# 07_-_CONNECTOR.net
KiCad netlist of a schematic drawn in Altium Designer
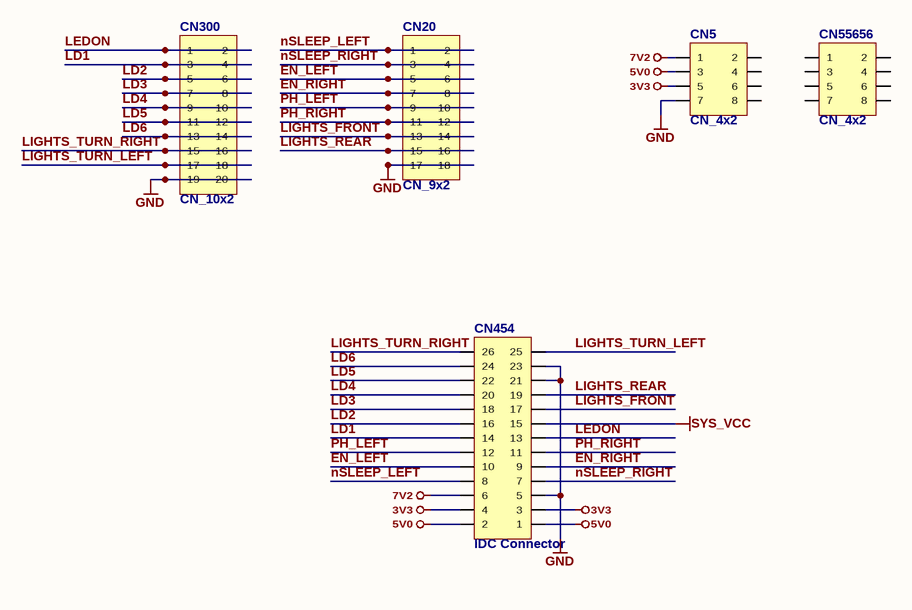
[diagram p0: [07] - CONNECTOR.SchDoc]

(export (version "E")
  (design (tool "Eeschema 10.0.6"))
  (components
    (comp (ref "CN5") (value "CN_4x2") (footprint "GP_4x2") (libsource (lib "goldpin_male") (part "CN_4x2")))
    (comp (ref "CN20") (value "CN_9x2") (footprint "GP_9x2") (libsource (lib "goldpin_male") (part "CN_9x2")))
    (comp (ref "CN300")
      (value "CN_10x2")
      (footprint "GP_10x2")
      (libsource (lib "goldpin_male") (part "CN_10x2"))
    )
    (comp (ref "CN454")
      (value "IDC Connector")
      (footprint "IDC26_RA")
      (libsource (lib "idc") (part "CN_13x2"))
    )
    (comp (ref "CN55656")
      (value "CN_4x2")
      (footprint "GP_4x2")
      (libsource (lib "goldpin_male") (part "CN_4x2"))
    )
  )
  (nets
    (net (code "1") (name "/EN_LEFT") (class "Default")
      (node (ref "CN20") (pin "5") (pinfunction "5_5") (pintype "passive"))
      (node (ref "CN20") (pin "6") (pinfunction "6_6") (pintype "passive"))
      (node (ref "CN454") (pin "10") (pinfunction "10_10") (pintype "passive"))
    )
    (net (code "2") (name "/EN_RIGHT") (class "Default")
      (node (ref "CN20") (pin "7") (pinfunction "7_7") (pintype "passive"))
      (node (ref "CN20") (pin "8") (pinfunction "8_8") (pintype "passive"))
      (node (ref "CN454") (pin "9") (pinfunction "9_9") (pintype "passive"))
    )
    (net (code "3") (name "/LD1") (class "Default")
      (node (ref "CN300") (pin "3") (pinfunction "3_3") (pintype "passive"))
      (node (ref "CN300") (pin "4") (pinfunction "4_4") (pintype "passive"))
      (node (ref "CN454") (pin "14") (pinfunction "14_14") (pintype "passive"))
    )
    (net (code "4") (name "/LD2") (class "Default")
      (node (ref "CN300") (pin "5") (pinfunction "5_5") (pintype "passive"))
      (node (ref "CN300") (pin "6") (pinfunction "6_6") (pintype "passive"))
      (node (ref "CN454") (pin "16") (pinfunction "16_16") (pintype "passive"))
    )
    (net (code "5") (name "/LD3") (class "Default")
      (node (ref "CN300") (pin "7") (pinfunction "7_7") (pintype "passive"))
      (node (ref "CN300") (pin "8") (pinfunction "8_8") (pintype "passive"))
      (node (ref "CN454") (pin "18") (pinfunction "18_18") (pintype "passive"))
    )
    (net (code "6") (name "/LD4") (class "Default")
      (node (ref "CN300") (pin "10") (pinfunction "10_10") (pintype "passive"))
      (node (ref "CN300") (pin "9") (pinfunction "9_9") (pintype "passive"))
      (node (ref "CN454") (pin "20") (pinfunction "20_20") (pintype "passive"))
    )
    (net (code "7") (name "/LD5") (class "Default")
      (node (ref "CN300") (pin "11") (pinfunction "11_11") (pintype "passive"))
      (node (ref "CN300") (pin "12") (pinfunction "12_12") (pintype "passive"))
      (node (ref "CN454") (pin "22") (pinfunction "22_22") (pintype "passive"))
    )
    (net (code "8") (name "/LD6") (class "Default")
      (node (ref "CN300") (pin "13") (pinfunction "13_13") (pintype "passive"))
      (node (ref "CN300") (pin "14") (pinfunction "14_14") (pintype "passive"))
      (node (ref "CN454") (pin "24") (pinfunction "24_24") (pintype "passive"))
    )
    (net (code "9") (name "/LEDON") (class "Default")
      (node (ref "CN300") (pin "1") (pinfunction "1_1") (pintype "passive"))
      (node (ref "CN300") (pin "2") (pinfunction "2_2") (pintype "passive"))
      (node (ref "CN454") (pin "13") (pinfunction "13_13") (pintype "passive"))
    )
    (net (code "10") (name "/LIGHTS_FRONT") (class "Default")
      (node (ref "CN20") (pin "13") (pinfunction "13_13") (pintype "passive"))
      (node (ref "CN20") (pin "14") (pinfunction "14_14") (pintype "passive"))
      (node (ref "CN454") (pin "17") (pinfunction "17_17") (pintype "passive"))
    )
    (net (code "11") (name "/LIGHTS_REAR") (class "Default")
      (node (ref "CN20") (pin "15") (pinfunction "15_15") (pintype "passive"))
      (node (ref "CN20") (pin "16") (pinfunction "16_16") (pintype "passive"))
      (node (ref "CN454") (pin "19") (pinfunction "19_19") (pintype "passive"))
    )
    (net (code "12") (name "/LIGHTS_TURN_LEFT") (class "Default")
      (node (ref "CN300") (pin "17") (pinfunction "17_17") (pintype "passive"))
      (node (ref "CN300") (pin "18") (pinfunction "18_18") (pintype "passive"))
      (node (ref "CN454") (pin "25") (pinfunction "25_25") (pintype "passive"))
    )
    (net (code "13") (name "/LIGHTS_TURN_RIGHT") (class "Default")
      (node (ref "CN300") (pin "15") (pinfunction "15_15") (pintype "passive"))
      (node (ref "CN300") (pin "16") (pinfunction "16_16") (pintype "passive"))
      (node (ref "CN454") (pin "26") (pinfunction "26_26") (pintype "passive"))
    )
    (net (code "14") (name "/PH_LEFT") (class "Default")
      (node (ref "CN20") (pin "10") (pinfunction "10_10") (pintype "passive"))
      (node (ref "CN20") (pin "9") (pinfunction "9_9") (pintype "passive"))
      (node (ref "CN454") (pin "12") (pinfunction "12_12") (pintype "passive"))
    )
    (net (code "15") (name "/PH_RIGHT") (class "Default")
      (node (ref "CN20") (pin "11") (pinfunction "11_11") (pintype "passive"))
      (node (ref "CN20") (pin "12") (pinfunction "12_12") (pintype "passive"))
      (node (ref "CN454") (pin "11") (pinfunction "11_11") (pintype "passive"))
    )
    (net (code "16") (name "/nSLEEP_LEFT") (class "Default")
      (node (ref "CN20") (pin "1") (pinfunction "1_1") (pintype "passive"))
      (node (ref "CN20") (pin "2") (pinfunction "2_2") (pintype "passive"))
      (node (ref "CN454") (pin "8") (pinfunction "8_8") (pintype "passive"))
    )
    (net (code "17") (name "/nSLEEP_RIGHT") (class "Default")
      (node (ref "CN20") (pin "3") (pinfunction "3_3") (pintype "passive"))
      (node (ref "CN20") (pin "4") (pinfunction "4_4") (pintype "passive"))
      (node (ref "CN454") (pin "7") (pinfunction "7_7") (pintype "passive"))
    )
    (net (code "18") (name "3V3") (class "Default")
      (node (ref "CN454") (pin "3") (pinfunction "3_3") (pintype "passive"))
      (node (ref "CN454") (pin "4") (pinfunction "4_4") (pintype "passive"))
      (node (ref "CN5") (pin "5") (pinfunction "5_5") (pintype "passive"))
    )
    (net (code "19") (name "5V0") (class "Default")
      (node (ref "CN454") (pin "1") (pinfunction "1_1") (pintype "passive"))
      (node (ref "CN454") (pin "2") (pinfunction "2_2") (pintype "passive"))
      (node (ref "CN5") (pin "3") (pinfunction "3_3") (pintype "passive"))
    )
    (net (code "20") (name "7V2") (class "Default")
      (node (ref "CN454") (pin "6") (pinfunction "6_6") (pintype "passive"))
      (node (ref "CN5") (pin "1") (pinfunction "1_1") (pintype "passive"))
    )
    (net (code "21") (name "GND") (class "Default")
      (node (ref "CN20") (pin "17") (pinfunction "17_17") (pintype "passive"))
      (node (ref "CN20") (pin "18") (pinfunction "18_18") (pintype "passive"))
      (node (ref "CN300") (pin "19") (pinfunction "19_19") (pintype "passive"))
      (node (ref "CN300") (pin "20") (pinfunction "20_20") (pintype "passive"))
      (node (ref "CN454") (pin "21") (pinfunction "21_21") (pintype "passive"))
      (node (ref "CN454") (pin "23") (pinfunction "23_23") (pintype "passive"))
      (node (ref "CN454") (pin "5") (pinfunction "5_5") (pintype "passive"))
      (node (ref "CN5") (pin "7") (pinfunction "7_7") (pintype "passive"))
    )
    (net (code "22") (name "SYS_VCC") (class "Default")
      (node (ref "CN454") (pin "15") (pinfunction "15_15") (pintype "passive"))
    )
    (net (code "23") (name "unconnected-(CN5-Pad2)") (class "Default")
      (node (ref "CN5") (pin "2") (pinfunction "2_2") (pintype "passive"))
    )
    (net (code "24") (name "unconnected-(CN5-Pad4)") (class "Default")
      (node (ref "CN5") (pin "4") (pinfunction "4_4") (pintype "passive"))
    )
    (net (code "25") (name "unconnected-(CN5-Pad6)") (class "Default")
      (node (ref "CN5") (pin "6") (pinfunction "6_6") (pintype "passive"))
    )
    (net (code "26") (name "unconnected-(CN5-Pad8)") (class "Default")
      (node (ref "CN5") (pin "8") (pinfunction "8_8") (pintype "passive"))
    )
    (net (code "27") (name "unconnected-(CN55656-Pad1)") (class "Default")
      (node (ref "CN55656") (pin "1") (pinfunction "1_1") (pintype "passive"))
    )
    (net (code "28") (name "unconnected-(CN55656-Pad2)") (class "Default")
      (node (ref "CN55656") (pin "2") (pinfunction "2_2") (pintype "passive"))
    )
    (net (code "29") (name "unconnected-(CN55656-Pad3)") (class "Default")
      (node (ref "CN55656") (pin "3") (pinfunction "3_3") (pintype "passive"))
    )
    (net (code "30") (name "unconnected-(CN55656-Pad4)") (class "Default")
      (node (ref "CN55656") (pin "4") (pinfunction "4_4") (pintype "passive"))
    )
    (net (code "31") (name "unconnected-(CN55656-Pad5)") (class "Default")
      (node (ref "CN55656") (pin "5") (pinfunction "5_5") (pintype "passive"))
    )
    (net (code "32") (name "unconnected-(CN55656-Pad6)") (class "Default")
      (node (ref "CN55656") (pin "6") (pinfunction "6_6") (pintype "passive"))
    )
    (net (code "33") (name "unconnected-(CN55656-Pad7)") (class "Default")
      (node (ref "CN55656") (pin "7") (pinfunction "7_7") (pintype "passive"))
    )
    (net (code "34") (name "unconnected-(CN55656-Pad8)") (class "Default")
      (node (ref "CN55656") (pin "8") (pinfunction "8_8") (pintype "passive"))
    )
  )
)
